# Motherboard_simple.net
KiCad netlist of a schematic drawn in EAGLE
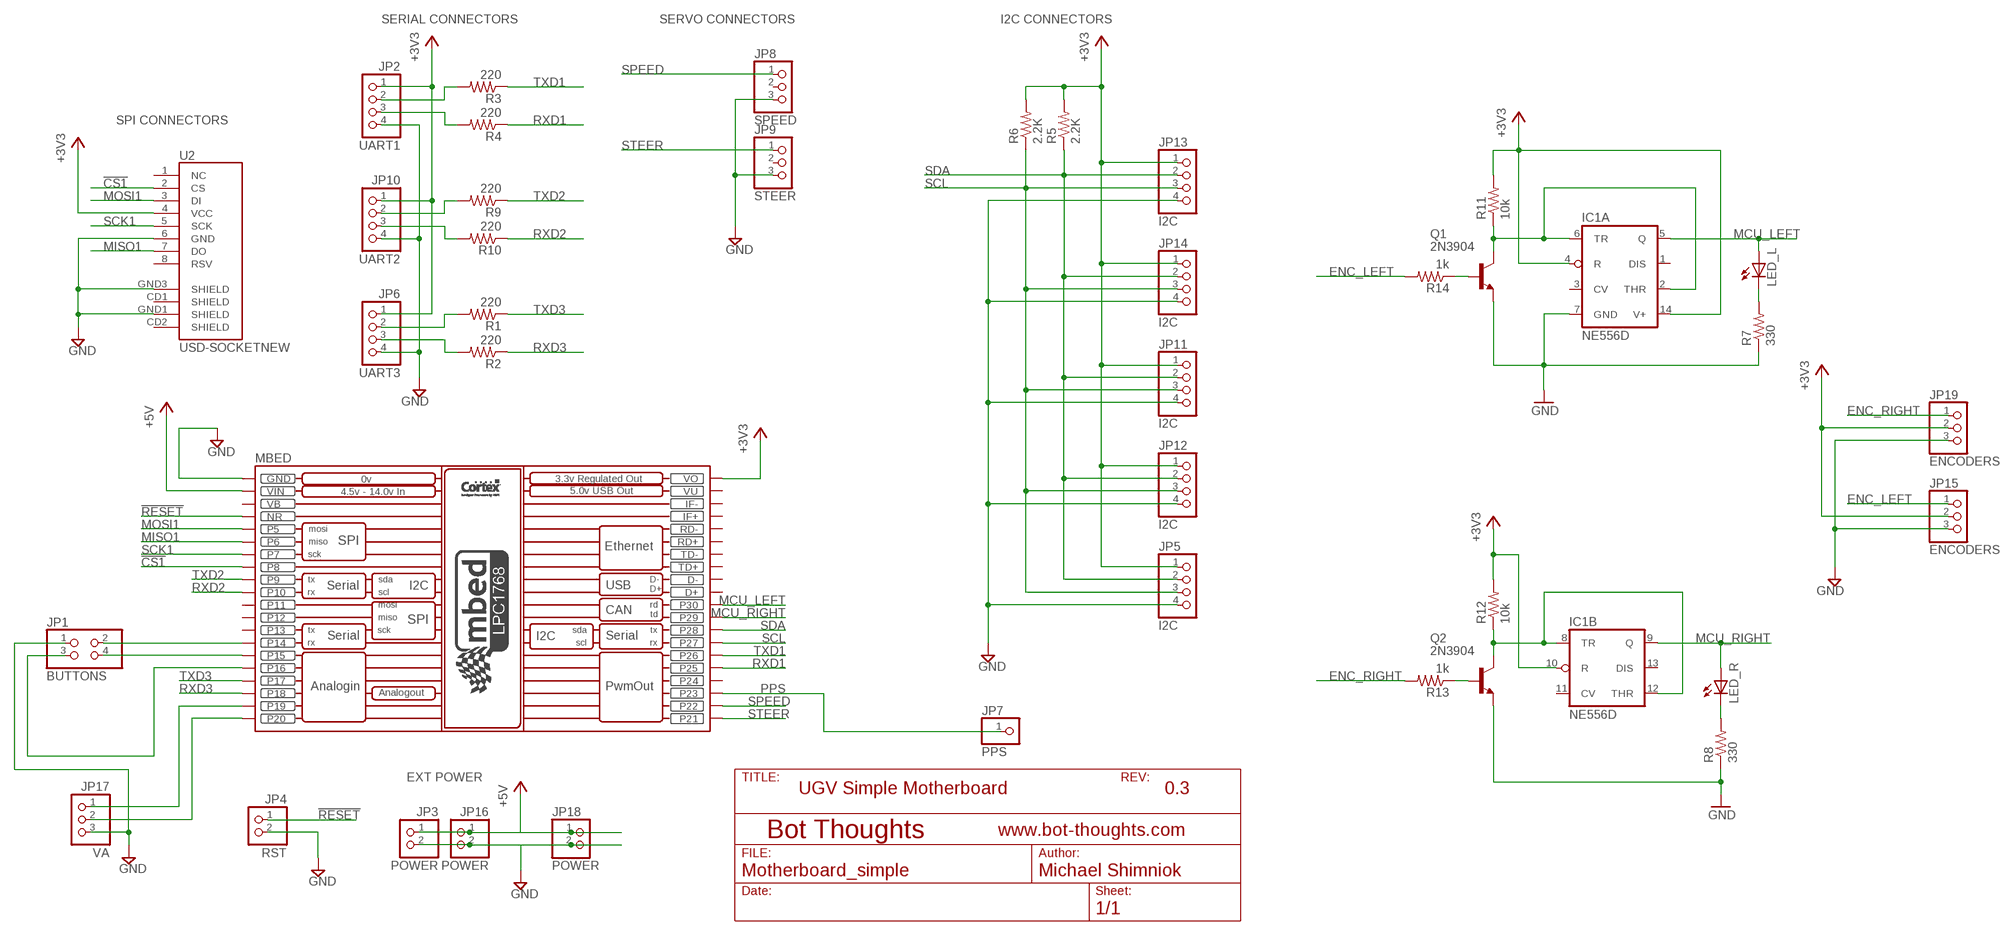
[diagram p0: schematic, sheet 1]

(export (version "E")
  (design (tool "Eeschema 10.0.6"))
  (components
    (comp (ref "IC1")
      (value "NE556D")
      (footprint "eagle-import:SO14")
      (libsource (lib "eagle-import") (part "556DNE"))
    )
    (comp (ref "JP1")
      (value "BUTTONS")
      (footprint "eagle-import:2X02")
      (libsource (lib "eagle-import") (part "PINHD-2X02_2.54"))
    )
    (comp (ref "JP2")
      (value "UART1")
      (footprint "eagle-import:1X04-S")
      (libsource (lib "eagle-import") (part "PINHD-1X04_2.54-S"))
    )
    (comp (ref "JP3")
      (value "POWER")
      (footprint "eagle-import:1X02-S")
      (libsource (lib "eagle-import") (part "PINHD-1X02_2.54-S"))
    )
    (comp (ref "JP4")
      (value "RST")
      (footprint "eagle-import:1X02-S")
      (libsource (lib "eagle-import") (part "PINHD-1X02_2.54-S"))
    )
    (comp (ref "JP5")
      (value "I2C")
      (footprint "eagle-import:1X04-S")
      (libsource (lib "eagle-import") (part "PINHD-1X04_2.54-S"))
    )
    (comp (ref "JP6")
      (value "UART3")
      (footprint "eagle-import:1X04-S")
      (libsource (lib "eagle-import") (part "PINHD-1X04_2.54-S"))
    )
    (comp (ref "JP7")
      (value "PPS")
      (footprint "eagle-import:1X01-S")
      (libsource (lib "eagle-import") (part "PINHD-1X01_2.54-S"))
    )
    (comp (ref "JP8")
      (value "SPEED")
      (footprint "eagle-import:1X03-S")
      (libsource (lib "eagle-import") (part "PINHD-1X03_2.54-S"))
    )
    (comp (ref "JP9")
      (value "STEER")
      (footprint "eagle-import:1X03-S")
      (libsource (lib "eagle-import") (part "PINHD-1X03_2.54-S"))
    )
    (comp (ref "JP10")
      (value "UART2")
      (footprint "eagle-import:1X04-S")
      (libsource (lib "eagle-import") (part "PINHD-1X04_2.54-S"))
    )
    (comp (ref "JP11")
      (value "I2C")
      (footprint "eagle-import:1X04-S")
      (libsource (lib "eagle-import") (part "PINHD-1X04_2.54-S"))
    )
    (comp (ref "JP12")
      (value "I2C")
      (footprint "eagle-import:1X04-S")
      (libsource (lib "eagle-import") (part "PINHD-1X04_2.54-S"))
    )
    (comp (ref "JP13")
      (value "I2C")
      (footprint "eagle-import:1X04-S")
      (libsource (lib "eagle-import") (part "PINHD-1X04_2.54-S"))
    )
    (comp (ref "JP14")
      (value "I2C")
      (footprint "eagle-import:1X04-S")
      (libsource (lib "eagle-import") (part "PINHD-1X04_2.54-S"))
    )
    (comp (ref "JP15")
      (value "ENCODERS")
      (footprint "eagle-import:1X03-S")
      (libsource (lib "eagle-import") (part "PINHD-1X03_2.54-S"))
    )
    (comp (ref "JP16")
      (value "POWER")
      (footprint "eagle-import:1X02-S")
      (libsource (lib "eagle-import") (part "PINHD-1X02_2.54-S"))
    )
    (comp (ref "JP17")
      (value "VA")
      (footprint "eagle-import:1X03-S")
      (libsource (lib "eagle-import") (part "PINHD-1X03_2.54-S"))
    )
    (comp (ref "JP18")
      (value "POWER")
      (footprint "eagle-import:1X02-S")
      (libsource (lib "eagle-import") (part "PINHD-1X02_2.54-S"))
    )
    (comp (ref "JP19")
      (value "ENCODERS")
      (footprint "eagle-import:1X03-S")
      (libsource (lib "eagle-import") (part "PINHD-1X03_2.54-S"))
    )
    (comp (ref "LED_L")
      (value "LED3MM")
      (footprint "eagle-import:LED3MM")
      (libsource (lib "eagle-import") (part "LED3MM"))
    )
    (comp (ref "LED_R")
      (value "LED3MM")
      (footprint "eagle-import:LED3MM")
      (libsource (lib "eagle-import") (part "LED3MM"))
    )
    (comp (ref "MBED")
      (value "MBED_NXP_LPC1768")
      (footprint "eagle-import:MBED-KIT")
      (fields (field (name "MPN") "2212S-20SG-85"))
      (libsource (lib "eagle-import") (part "MBED_NXP_LPC1768"))
    )
    (comp (ref "Q1")
      (value "2N3904")
      (footprint "eagle-import:TO92-CBE")
      (libsource (lib "eagle-import") (part "2N3904INLINE"))
    )
    (comp (ref "Q2")
      (value "2N3904")
      (footprint "eagle-import:TO92-CBE")
      (libsource (lib "eagle-import") (part "2N3904INLINE"))
    )
    (comp (ref "R1")
      (value "220")
      (footprint "eagle-import:0204_5")
      (fields (field (name "MPN") "WCR0805-220RFI"))
      (libsource (lib "eagle-import") (part "R-US_0204/5"))
    )
    (comp (ref "R2")
      (value "220")
      (footprint "eagle-import:0204_5")
      (fields (field (name "MPN") "WCR0805-220RFI"))
      (libsource (lib "eagle-import") (part "R-US_0204/5"))
    )
    (comp (ref "R3")
      (value "220")
      (footprint "eagle-import:0204_5")
      (fields (field (name "MPN") "WCR0805-220RFI"))
      (libsource (lib "eagle-import") (part "R-US_0204/5"))
    )
    (comp (ref "R4")
      (value "220")
      (footprint "eagle-import:0204_5")
      (fields (field (name "MPN") "WCR0805-220RFI"))
      (libsource (lib "eagle-import") (part "R-US_0204/5"))
    )
    (comp (ref "R5")
      (value "2.2K")
      (footprint "eagle-import:0204_5")
      (libsource (lib "eagle-import") (part "R-US_0204/5"))
    )
    (comp (ref "R6")
      (value "2.2K")
      (footprint "eagle-import:0204_5")
      (libsource (lib "eagle-import") (part "R-US_0204/5"))
    )
    (comp (ref "R7")
      (value "330")
      (footprint "eagle-import:0204_5")
      (libsource (lib "eagle-import") (part "R-US_0204/5"))
    )
    (comp (ref "R8")
      (value "330")
      (footprint "eagle-import:0204_5")
      (libsource (lib "eagle-import") (part "R-US_0204/5"))
    )
    (comp (ref "R9")
      (value "220")
      (footprint "eagle-import:0204_5")
      (fields (field (name "MPN") "WCR0805-220RFI"))
      (libsource (lib "eagle-import") (part "R-US_0204/5"))
    )
    (comp (ref "R10")
      (value "220")
      (footprint "eagle-import:0204_5")
      (fields (field (name "MPN") "WCR0805-220RFI"))
      (libsource (lib "eagle-import") (part "R-US_0204/5"))
    )
    (comp (ref "R11")
      (value "10k")
      (footprint "eagle-import:0204_5")
      (libsource (lib "eagle-import") (part "R-US_0204/5"))
    )
    (comp (ref "R12")
      (value "10k")
      (footprint "eagle-import:0204_5")
      (libsource (lib "eagle-import") (part "R-US_0204/5"))
    )
    (comp (ref "R13")
      (value "1k")
      (footprint "eagle-import:0204_5")
      (libsource (lib "eagle-import") (part "R-US_0204/5"))
    )
    (comp (ref "R14")
      (value "1k")
      (footprint "eagle-import:0204_5")
      (libsource (lib "eagle-import") (part "R-US_0204/5"))
    )
    (comp (ref "U2")
      (value "USD-SOCKETNEW")
      (footprint "eagle-import:MICRO-SD-SOCKET-PP")
      (libsource (lib "eagle-import") (part "USD-SOCKETNEW"))
    )
  )
  (nets
    (net (code "1") (name "+3V3") (class "Default")
      (node (ref "IC1") (pin "10") (pinfunction "R_10") (pintype "input"))
      (node (ref "IC1") (pin "14") (pinfunction "V+_14") (pintype "power_in"))
      (node (ref "IC1") (pin "4") (pinfunction "R_4") (pintype "input"))
      (node (ref "JP10") (pin "1") (pinfunction "1_1") (pintype "passive"))
      (node (ref "JP11") (pin "1") (pinfunction "1_1") (pintype "passive"))
      (node (ref "JP12") (pin "1") (pinfunction "1_1") (pintype "passive"))
      (node (ref "JP13") (pin "1") (pinfunction "1_1") (pintype "passive"))
      (node (ref "JP14") (pin "1") (pinfunction "1_1") (pintype "passive"))
      (node (ref "JP15") (pin "2") (pinfunction "2_2") (pintype "passive"))
      (node (ref "JP19") (pin "2") (pinfunction "2_2") (pintype "passive"))
      (node (ref "JP2") (pin "1") (pinfunction "1_1") (pintype "passive"))
      (node (ref "JP5") (pin "1") (pinfunction "1_1") (pintype "passive"))
      (node (ref "JP6") (pin "1") (pinfunction "1_1") (pintype "passive"))
      (node (ref "MBED") (pin "VOUT") (pinfunction "VO_VOUT") (pintype "power_in"))
      (node (ref "R11") (pin "2") (pinfunction "2_2") (pintype "passive"))
      (node (ref "R12") (pin "2") (pinfunction "2_2") (pintype "passive"))
      (node (ref "R5") (pin "2") (pinfunction "2_2") (pintype "passive"))
      (node (ref "R6") (pin "2") (pinfunction "2_2") (pintype "passive"))
      (node (ref "U2") (pin "4") (pinfunction "VCC_4") (pintype "bidirectional"))
    )
    (net (code "2") (name "+5V") (class "Default")
      (node (ref "JP16") (pin "1") (pinfunction "1_1") (pintype "passive"))
      (node (ref "JP18") (pin "1") (pinfunction "1_1") (pintype "passive"))
      (node (ref "JP3") (pin "1") (pinfunction "1_1") (pintype "passive"))
      (node (ref "MBED") (pin "VIN") (pinfunction "VIN_VIN") (pintype "power_in"))
    )
    (net (code "3") (name "/ENC_LEFT") (class "Default")
      (node (ref "JP15") (pin "1") (pinfunction "1_1") (pintype "passive"))
      (node (ref "R14") (pin "2") (pinfunction "2_2") (pintype "passive"))
    )
    (net (code "4") (name "/ENC_RIGHT") (class "Default")
      (node (ref "JP19") (pin "1") (pinfunction "1_1") (pintype "passive"))
      (node (ref "R13") (pin "2") (pinfunction "2_2") (pintype "passive"))
    )
    (net (code "5") (name "/MCU_LEFT") (class "Default")
      (node (ref "IC1") (pin "5") (pinfunction "Q_5") (pintype "output"))
      (node (ref "LED_L") (pin "A") (pinfunction "A_A") (pintype "passive"))
      (node (ref "MBED") (pin "P$30") (pinfunction "P30_P$30") (pintype "bidirectional"))
    )
    (net (code "6") (name "/MCU_RIGHT") (class "Default")
      (node (ref "IC1") (pin "9") (pinfunction "Q_9") (pintype "output"))
      (node (ref "LED_R") (pin "A") (pinfunction "A_A") (pintype "passive"))
      (node (ref "MBED") (pin "P$29") (pinfunction "P29_P$29") (pintype "bidirectional"))
    )
    (net (code "7") (name "/MISO1") (class "Default")
      (node (ref "MBED") (pin "P$6") (pinfunction "P6_P$6") (pintype "bidirectional"))
      (node (ref "U2") (pin "7") (pinfunction "DO_7") (pintype "bidirectional"))
    )
    (net (code "8") (name "/MOSI1") (class "Default")
      (node (ref "MBED") (pin "P$5") (pinfunction "P5_P$5") (pintype "bidirectional"))
      (node (ref "U2") (pin "3") (pinfunction "DI_3") (pintype "bidirectional"))
    )
    (net (code "9") (name "/PPS") (class "Default")
      (node (ref "JP7") (pin "1") (pinfunction "1_1") (pintype "passive"))
      (node (ref "MBED") (pin "P$23") (pinfunction "P23_P$23") (pintype "bidirectional"))
    )
    (net (code "10") (name "/RXD1") (class "Default")
      (node (ref "MBED") (pin "P$25") (pinfunction "P25_P$25") (pintype "bidirectional"))
      (node (ref "R4") (pin "1") (pinfunction "1_1") (pintype "passive"))
    )
    (net (code "11") (name "/RXD2") (class "Default")
      (node (ref "MBED") (pin "P$10") (pinfunction "P10_P$10") (pintype "bidirectional"))
      (node (ref "R10") (pin "1") (pinfunction "1_1") (pintype "passive"))
    )
    (net (code "12") (name "/RXD3") (class "Default")
      (node (ref "MBED") (pin "P$18") (pinfunction "P18_P$18") (pintype "bidirectional"))
      (node (ref "R2") (pin "1") (pinfunction "1_1") (pintype "passive"))
    )
    (net (code "13") (name "/SCK1") (class "Default")
      (node (ref "MBED") (pin "P$7") (pinfunction "P7_P$7") (pintype "bidirectional"))
      (node (ref "U2") (pin "5") (pinfunction "SCK_5") (pintype "bidirectional"))
    )
    (net (code "14") (name "/SCL") (class "Default")
      (node (ref "JP11") (pin "3") (pinfunction "3_3") (pintype "passive"))
      (node (ref "JP12") (pin "3") (pinfunction "3_3") (pintype "passive"))
      (node (ref "JP13") (pin "3") (pinfunction "3_3") (pintype "passive"))
      (node (ref "JP14") (pin "3") (pinfunction "3_3") (pintype "passive"))
      (node (ref "JP5") (pin "3") (pinfunction "3_3") (pintype "passive"))
      (node (ref "MBED") (pin "P$27") (pinfunction "P27_P$27") (pintype "bidirectional"))
      (node (ref "R6") (pin "1") (pinfunction "1_1") (pintype "passive"))
    )
    (net (code "15") (name "/SDA") (class "Default")
      (node (ref "JP11") (pin "2") (pinfunction "2_2") (pintype "passive"))
      (node (ref "JP12") (pin "2") (pinfunction "2_2") (pintype "passive"))
      (node (ref "JP13") (pin "2") (pinfunction "2_2") (pintype "passive"))
      (node (ref "JP14") (pin "2") (pinfunction "2_2") (pintype "passive"))
      (node (ref "JP5") (pin "2") (pinfunction "2_2") (pintype "passive"))
      (node (ref "MBED") (pin "P$28") (pinfunction "P28_P$28") (pintype "bidirectional"))
      (node (ref "R5") (pin "1") (pinfunction "1_1") (pintype "passive"))
    )
    (net (code "16") (name "/SPEED") (class "Default")
      (node (ref "JP8") (pin "1") (pinfunction "1_1") (pintype "passive"))
      (node (ref "MBED") (pin "P$22") (pinfunction "P22_P$22") (pintype "bidirectional"))
    )
    (net (code "17") (name "/STEER") (class "Default")
      (node (ref "JP9") (pin "1") (pinfunction "1_1") (pintype "passive"))
      (node (ref "MBED") (pin "P$21") (pinfunction "P21_P$21") (pintype "bidirectional"))
    )
    (net (code "18") (name "/TXD1") (class "Default")
      (node (ref "MBED") (pin "P$26") (pinfunction "P26_P$26") (pintype "bidirectional"))
      (node (ref "R3") (pin "1") (pinfunction "1_1") (pintype "passive"))
    )
    (net (code "19") (name "/TXD2") (class "Default")
      (node (ref "MBED") (pin "P$9") (pinfunction "P9_P$9") (pintype "bidirectional"))
      (node (ref "R9") (pin "1") (pinfunction "1_1") (pintype "passive"))
    )
    (net (code "20") (name "/TXD3") (class "Default")
      (node (ref "MBED") (pin "P$17") (pinfunction "P17_P$17") (pintype "bidirectional"))
      (node (ref "R1") (pin "1") (pinfunction "1_1") (pintype "passive"))
    )
    (net (code "21") (name "/VB") (class "Default")
      (node (ref "MBED") (pin "VB") (pinfunction "VB_VB") (pintype "power_in"))
    )
    (net (code "22") (name "/VU") (class "Default")
      (node (ref "MBED") (pin "VU") (pinfunction "VU_VU") (pintype "power_in"))
    )
    (net (code "23") (name "/~{CS1}") (class "Default")
      (node (ref "MBED") (pin "P$8") (pinfunction "P8_P$8") (pintype "bidirectional"))
      (node (ref "U2") (pin "2") (pinfunction "CS_2") (pintype "bidirectional"))
    )
    (net (code "24") (name "/~{RESET}") (class "Default")
      (node (ref "JP4") (pin "1") (pinfunction "1_1") (pintype "passive"))
      (node (ref "MBED") (pin "NR") (pinfunction "NR_NR") (pintype "power_in"))
    )
    (net (code "25") (name "GND") (class "Default")
      (node (ref "IC1") (pin "7") (pinfunction "GND_7") (pintype "power_in"))
      (node (ref "JP1") (pin "1") (pinfunction "1_1") (pintype "passive"))
      (node (ref "JP10") (pin "4") (pinfunction "4_4") (pintype "passive"))
      (node (ref "JP11") (pin "4") (pinfunction "4_4") (pintype "passive"))
      (node (ref "JP12") (pin "4") (pinfunction "4_4") (pintype "passive"))
      (node (ref "JP13") (pin "4") (pinfunction "4_4") (pintype "passive"))
      (node (ref "JP14") (pin "4") (pinfunction "4_4") (pintype "passive"))
      (node (ref "JP15") (pin "3") (pinfunction "3_3") (pintype "passive"))
      (node (ref "JP16") (pin "2") (pinfunction "2_2") (pintype "passive"))
      (node (ref "JP17") (pin "3") (pinfunction "3_3") (pintype "passive"))
      (node (ref "JP18") (pin "2") (pinfunction "2_2") (pintype "passive"))
      (node (ref "JP19") (pin "3") (pinfunction "3_3") (pintype "passive"))
      (node (ref "JP2") (pin "4") (pinfunction "4_4") (pintype "passive"))
      (node (ref "JP3") (pin "2") (pinfunction "2_2") (pintype "passive"))
      (node (ref "JP4") (pin "2") (pinfunction "2_2") (pintype "passive"))
      (node (ref "JP5") (pin "4") (pinfunction "4_4") (pintype "passive"))
      (node (ref "JP6") (pin "4") (pinfunction "4_4") (pintype "passive"))
      (node (ref "JP8") (pin "3") (pinfunction "3_3") (pintype "passive"))
      (node (ref "JP9") (pin "3") (pinfunction "3_3") (pintype "passive"))
      (node (ref "MBED") (pin "GND") (pinfunction "GND_GND") (pintype "power_in"))
      (node (ref "Q1") (pin "E") (pinfunction "E_E") (pintype "passive"))
      (node (ref "Q2") (pin "E") (pinfunction "E_E") (pintype "passive"))
      (node (ref "R7") (pin "1") (pinfunction "1_1") (pintype "passive"))
      (node (ref "R8") (pin "1") (pinfunction "1_1") (pintype "passive"))
      (node (ref "U2") (pin "6") (pinfunction "GND_6") (pintype "bidirectional"))
      (node (ref "U2") (pin "GND1") (pinfunction "SHIELD_GND1") (pintype "bidirectional"))
      (node (ref "U2") (pin "GND3") (pinfunction "SHIELD_GND3") (pintype "bidirectional"))
    )
    (net (code "26") (name "Net-(IC1A-THR)") (class "Default")
      (node (ref "IC1") (pin "2") (pinfunction "THR_2") (pintype "input"))
      (node (ref "IC1") (pin "6") (pinfunction "TR_6") (pintype "input"))
      (node (ref "Q1") (pin "C") (pinfunction "C_C") (pintype "passive"))
      (node (ref "R11") (pin "1") (pinfunction "1_1") (pintype "passive"))
    )
    (net (code "27") (name "Net-(IC1B-THR)") (class "Default")
      (node (ref "IC1") (pin "12") (pinfunction "THR_12") (pintype "input"))
      (node (ref "IC1") (pin "8") (pinfunction "TR_8") (pintype "input"))
      (node (ref "Q2") (pin "C") (pinfunction "C_C") (pintype "passive"))
      (node (ref "R12") (pin "1") (pinfunction "1_1") (pintype "passive"))
    )
    (net (code "28") (name "Net-(JP2-Pad2)") (class "Default")
      (node (ref "JP2") (pin "2") (pinfunction "2_2") (pintype "passive"))
      (node (ref "R3") (pin "2") (pinfunction "2_2") (pintype "passive"))
    )
    (net (code "29") (name "Net-(JP2-Pad3)") (class "Default")
      (node (ref "JP2") (pin "3") (pinfunction "3_3") (pintype "passive"))
      (node (ref "R4") (pin "2") (pinfunction "2_2") (pintype "passive"))
    )
    (net (code "30") (name "Net-(JP6-Pad2)") (class "Default")
      (node (ref "JP6") (pin "2") (pinfunction "2_2") (pintype "passive"))
      (node (ref "R1") (pin "2") (pinfunction "2_2") (pintype "passive"))
    )
    (net (code "31") (name "Net-(JP6-Pad3)") (class "Default")
      (node (ref "JP6") (pin "3") (pinfunction "3_3") (pintype "passive"))
      (node (ref "R2") (pin "2") (pinfunction "2_2") (pintype "passive"))
    )
    (net (code "32") (name "Net-(JP10-Pad2)") (class "Default")
      (node (ref "JP10") (pin "2") (pinfunction "2_2") (pintype "passive"))
      (node (ref "R9") (pin "2") (pinfunction "2_2") (pintype "passive"))
    )
    (net (code "33") (name "Net-(JP10-Pad3)") (class "Default")
      (node (ref "JP10") (pin "3") (pinfunction "3_3") (pintype "passive"))
      (node (ref "R10") (pin "2") (pinfunction "2_2") (pintype "passive"))
    )
    (net (code "34") (name "Net-(LED_L-C)") (class "Default")
      (node (ref "LED_L") (pin "K") (pinfunction "C_K") (pintype "passive"))
      (node (ref "R7") (pin "2") (pinfunction "2_2") (pintype "passive"))
    )
    (net (code "35") (name "Net-(LED_R-C)") (class "Default")
      (node (ref "LED_R") (pin "K") (pinfunction "C_K") (pintype "passive"))
      (node (ref "R8") (pin "2") (pinfunction "2_2") (pintype "passive"))
    )
    (net (code "36") (name "Net-(MBED-P14)") (class "Default")
      (node (ref "JP1") (pin "2") (pinfunction "2_2") (pintype "passive"))
      (node (ref "MBED") (pin "P$14") (pinfunction "P14_P$14") (pintype "bidirectional"))
    )
    (net (code "37") (name "Net-(MBED-P15)") (class "Default")
      (node (ref "JP1") (pin "4") (pinfunction "4_4") (pintype "passive"))
      (node (ref "MBED") (pin "P$15") (pinfunction "P15_P$15") (pintype "bidirectional"))
    )
    (net (code "38") (name "Net-(MBED-P16)") (class "Default")
      (node (ref "JP1") (pin "3") (pinfunction "3_3") (pintype "passive"))
      (node (ref "MBED") (pin "P$16") (pinfunction "P16_P$16") (pintype "bidirectional"))
    )
    (net (code "39") (name "Net-(MBED-P19)") (class "Default")
      (node (ref "JP17") (pin "1") (pinfunction "1_1") (pintype "passive"))
      (node (ref "MBED") (pin "P$19") (pinfunction "P19_P$19") (pintype "bidirectional"))
    )
    (net (code "40") (name "Net-(MBED-P20)") (class "Default")
      (node (ref "JP17") (pin "2") (pinfunction "2_2") (pintype "passive"))
      (node (ref "MBED") (pin "P$20") (pinfunction "P20_P$20") (pintype "bidirectional"))
    )
    (net (code "41") (name "Net-(Q1-PadB)") (class "Default")
      (node (ref "Q1") (pin "B") (pinfunction "B_B") (pintype "passive"))
      (node (ref "R14") (pin "1") (pinfunction "1_1") (pintype "passive"))
    )
    (net (code "42") (name "Net-(Q2-PadB)") (class "Default")
      (node (ref "Q2") (pin "B") (pinfunction "B_B") (pintype "passive"))
      (node (ref "R13") (pin "1") (pinfunction "1_1") (pintype "passive"))
    )
    (net (code "43") (name "unconnected-(IC1A-CV-Pad3)") (class "Default")
      (node (ref "IC1") (pin "3") (pinfunction "CV_3") (pintype "input"))
    )
    (net (code "44") (name "unconnected-(IC1A-DIS-Pad1)") (class "Default")
      (node (ref "IC1") (pin "1") (pinfunction "DIS_1") (pintype "input"))
    )
    (net (code "45") (name "unconnected-(IC1B-CV-Pad11)") (class "Default")
      (node (ref "IC1") (pin "11") (pinfunction "CV_11") (pintype "input"))
    )
    (net (code "46") (name "unconnected-(IC1B-DIS-Pad13)") (class "Default")
      (node (ref "IC1") (pin "13") (pinfunction "DIS_13") (pintype "input"))
    )
    (net (code "47") (name "unconnected-(JP8-Pad2)") (class "Default")
      (node (ref "JP8") (pin "2") (pinfunction "2_2") (pintype "passive"))
    )
    (net (code "48") (name "unconnected-(JP9-Pad2)") (class "Default")
      (node (ref "JP9") (pin "2") (pinfunction "2_2") (pintype "passive"))
    )
    (net (code "49") (name "unconnected-(MBED-P11-PadP$11)") (class "Default")
      (node (ref "MBED") (pin "P$11") (pinfunction "P11_P$11") (pintype "bidirectional"))
    )
    (net (code "50") (name "unconnected-(MBED-P12-PadP$12)") (class "Default")
      (node (ref "MBED") (pin "P$12") (pinfunction "P12_P$12") (pintype "bidirectional"))
    )
    (net (code "51") (name "unconnected-(MBED-P13-PadP$13)") (class "Default")
      (node (ref "MBED") (pin "P$13") (pinfunction "P13_P$13") (pintype "bidirectional"))
    )
    (net (code "52") (name "unconnected-(MBED-P24-PadP$24)") (class "Default")
      (node (ref "MBED") (pin "P$24") (pinfunction "P24_P$24") (pintype "bidirectional"))
    )
    (net (code "53") (name "unconnected-(MBED-PadD+)") (class "Default")
      (node (ref "MBED") (pin "D+") (pinfunction "D+_D+") (pintype "bidirectional"))
    )
    (net (code "54") (name "unconnected-(MBED-PadD-)") (class "Default")
      (node (ref "MBED") (pin "D-") (pinfunction "D-_D-") (pintype "bidirectional"))
    )
    (net (code "55") (name "unconnected-(MBED-PadIF+)") (class "Default")
      (node (ref "MBED") (pin "IF+") (pinfunction "IF+_IF+") (pintype "bidirectional"))
    )
    (net (code "56") (name "unconnected-(MBED-PadIF-)") (class "Default")
      (node (ref "MBED") (pin "IF-") (pinfunction "IF-_IF-") (pintype "bidirectional"))
    )
    (net (code "57") (name "unconnected-(MBED-PadRD+)") (class "Default")
      (node (ref "MBED") (pin "RD+") (pinfunction "RD+_RD+") (pintype "bidirectional"))
    )
    (net (code "58") (name "unconnected-(MBED-PadRD-)") (class "Default")
      (node (ref "MBED") (pin "RD-") (pinfunction "RD-_RD-") (pintype "bidirectional"))
    )
    (net (code "59") (name "unconnected-(MBED-PadTD+)") (class "Default")
      (node (ref "MBED") (pin "TD+") (pinfunction "TD+_TD+") (pintype "bidirectional"))
    )
    (net (code "60") (name "unconnected-(MBED-PadTD-)") (class "Default")
      (node (ref "MBED") (pin "TD-") (pinfunction "TD-_TD-") (pintype "bidirectional"))
    )
    (net (code "61") (name "unconnected-(U2-NC-Pad1)") (class "Default")
      (node (ref "U2") (pin "1") (pinfunction "NC_1") (pintype "bidirectional"))
    )
    (net (code "62") (name "unconnected-(U2-RSV-Pad8)") (class "Default")
      (node (ref "U2") (pin "8") (pinfunction "RSV_8") (pintype "bidirectional"))
    )
    (net (code "63") (name "unconnected-(U2-SHIELD-PadCD1)") (class "Default")
      (node (ref "U2") (pin "CD1") (pinfunction "SHIELD_CD1") (pintype "bidirectional"))
    )
    (net (code "64") (name "unconnected-(U2-SHIELD-PadCD2)") (class "Default")
      (node (ref "U2") (pin "CD2") (pinfunction "SHIELD_CD2") (pintype "bidirectional"))
    )
  )
)
